# LED_SEQUENCER.net
KiCad netlist of a schematic drawn in Altium Designer
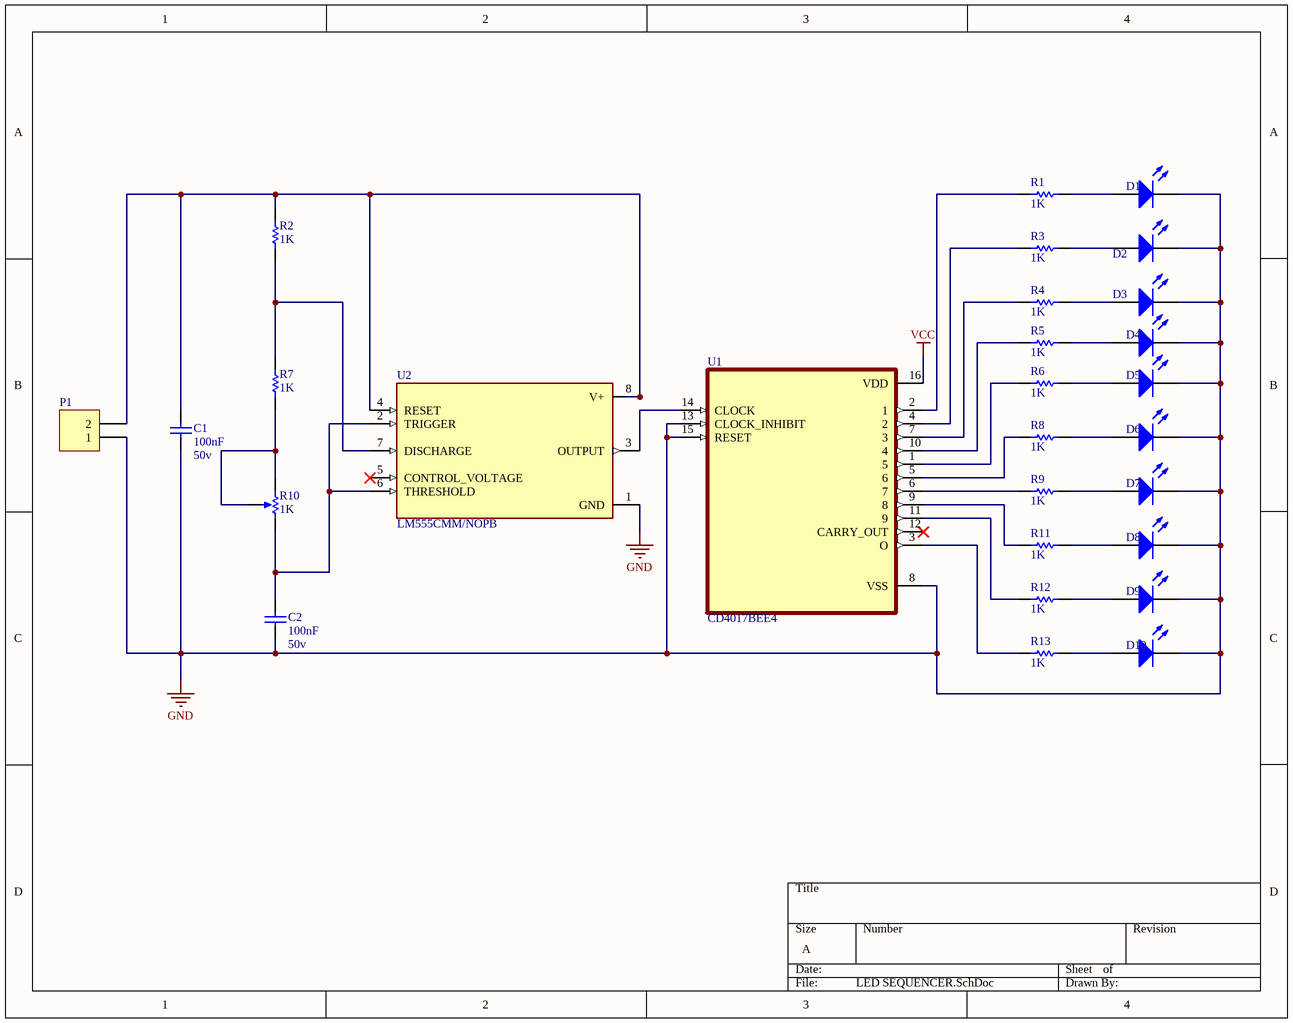
[diagram p0: LED SEQUENCER.SchDoc]

(export (version "E")
  (design (tool "Eeschema 10.0.6"))
  (components
    (comp (ref "C1")
      (value "100nF")
      (footprint "MY_0603")
      (description "None polar capacitor")
      (fields (field (name "ASID PART NUMBER") "C-AS") (field (name "VOLTE") "50v"))
      (libsource (lib "3. Mylib with 3d body") (part "Cap ceramic"))
    )
    (comp (ref "C2")
      (value "100nF")
      (footprint "MY_0603")
      (description "None polar capacitor")
      (fields (field (name "ASID PART NUMBER") "C-AS") (field (name "VOLTE") "50v"))
      (libsource (lib "3. Mylib with 3d body") (part "Cap ceramic"))
    )
    (comp (ref "D1")
      (value "~")
      (footprint "MY_LED_0805")
      (description "Typical INFRARED GaAs LED")
      (fields (field (name "ASID PART NUMBER") "LED-AS"))
      (libsource (lib "3. Mylib with 3d body") (part "LED"))
    )
    (comp (ref "D2")
      (value "~")
      (footprint "MY_LED_0805")
      (description "Typical INFRARED GaAs LED")
      (fields (field (name "ASID PART NUMBER") "LED-AS"))
      (libsource (lib "3. Mylib with 3d body") (part "LED"))
    )
    (comp (ref "D3")
      (value "~")
      (footprint "MY_LED_0805")
      (description "Typical INFRARED GaAs LED")
      (fields (field (name "ASID PART NUMBER") "LED-AS"))
      (libsource (lib "3. Mylib with 3d body") (part "LED"))
    )
    (comp (ref "D4")
      (value "~")
      (footprint "MY_LED_0805")
      (description "Typical INFRARED GaAs LED")
      (fields (field (name "ASID PART NUMBER") "LED-AS"))
      (libsource (lib "3. Mylib with 3d body") (part "LED"))
    )
    (comp (ref "D5")
      (value "~")
      (footprint "MY_LED_0805")
      (description "Typical INFRARED GaAs LED")
      (fields (field (name "ASID PART NUMBER") "LED-AS"))
      (libsource (lib "3. Mylib with 3d body") (part "LED"))
    )
    (comp (ref "D6")
      (value "~")
      (footprint "MY_LED_0805")
      (description "Typical INFRARED GaAs LED")
      (fields (field (name "ASID PART NUMBER") "LED-AS"))
      (libsource (lib "3. Mylib with 3d body") (part "LED"))
    )
    (comp (ref "D7")
      (value "~")
      (footprint "MY_LED_0805")
      (description "Typical INFRARED GaAs LED")
      (fields (field (name "ASID PART NUMBER") "LED-AS"))
      (libsource (lib "3. Mylib with 3d body") (part "LED"))
    )
    (comp (ref "D8")
      (value "~")
      (footprint "MY_LED_0805")
      (description "Typical INFRARED GaAs LED")
      (fields (field (name "ASID PART NUMBER") "LED-AS"))
      (libsource (lib "3. Mylib with 3d body") (part "LED"))
    )
    (comp (ref "D9")
      (value "~")
      (footprint "MY_LED_0805")
      (description "Typical INFRARED GaAs LED")
      (fields (field (name "ASID PART NUMBER") "LED-AS"))
      (libsource (lib "3. Mylib with 3d body") (part "LED"))
    )
    (comp (ref "D10")
      (value "~")
      (footprint "MY_LED_0805")
      (description "Typical INFRARED GaAs LED")
      (fields (field (name "ASID PART NUMBER") "LED-AS"))
      (libsource (lib "3. Mylib with 3d body") (part "LED"))
    )
    (comp (ref "P1")
      (value "Header 2")
      (footprint "MY_FE02")
      (description "Header, 2-Pin")
      (fields (field (name "ASID PART NUMBER") "Header 2-AS"))
      (libsource (lib "3. Mylib with 3d body") (part "Header 2"))
    )
    (comp (ref "R1")
      (value "1K")
      (footprint "MY_0603")
      (description "Standard resistor")
      (fields (field (name "ASID PART NUMBER") "Res-AS"))
      (libsource (lib "3. Mylib with 3d body") (part "Res"))
    )
    (comp (ref "R2")
      (value "1K")
      (footprint "MY_0603")
      (description "Standard resistor")
      (fields (field (name "ASID PART NUMBER") "Res-AS"))
      (libsource (lib "3. Mylib with 3d body") (part "Res"))
    )
    (comp (ref "R3")
      (value "1K")
      (footprint "MY_0603")
      (description "Standard resistor")
      (fields (field (name "ASID PART NUMBER") "Res-AS"))
      (libsource (lib "3. Mylib with 3d body") (part "Res"))
    )
    (comp (ref "R4")
      (value "1K")
      (footprint "MY_0603")
      (description "Standard resistor")
      (fields (field (name "ASID PART NUMBER") "Res-AS"))
      (libsource (lib "3. Mylib with 3d body") (part "Res"))
    )
    (comp (ref "R5")
      (value "1K")
      (footprint "MY_0603")
      (description "Standard resistor")
      (fields (field (name "ASID PART NUMBER") "Res-AS"))
      (libsource (lib "3. Mylib with 3d body") (part "Res"))
    )
    (comp (ref "R6")
      (value "1K")
      (footprint "MY_0603")
      (description "Standard resistor")
      (fields (field (name "ASID PART NUMBER") "Res-AS"))
      (libsource (lib "3. Mylib with 3d body") (part "Res"))
    )
    (comp (ref "R7")
      (value "1K")
      (footprint "MY_0603")
      (description "Standard resistor")
      (fields (field (name "ASID PART NUMBER") "Res-AS"))
      (libsource (lib "3. Mylib with 3d body") (part "Res"))
    )
    (comp (ref "R8")
      (value "1K")
      (footprint "MY_0603")
      (description "Standard resistor")
      (fields (field (name "ASID PART NUMBER") "Res-AS"))
      (libsource (lib "3. Mylib with 3d body") (part "Res"))
    )
    (comp (ref "R9")
      (value "1K")
      (footprint "MY_0603")
      (description "Standard resistor")
      (fields (field (name "ASID PART NUMBER") "Res-AS"))
      (libsource (lib "3. Mylib with 3d body") (part "Res"))
    )
    (comp (ref "R10")
      (value "1K")
      (footprint "My_Pot")
      (description "Potentiometer")
      (fields (field (name "ASID PART NUMBER") "Variable Resistor-AS"))
      (libsource (lib "3. Mylib with 3d body") (part "Variable Resistor"))
    )
    (comp (ref "R11")
      (value "1K")
      (footprint "MY_0603")
      (description "Standard resistor")
      (fields (field (name "ASID PART NUMBER") "Res-AS"))
      (libsource (lib "3. Mylib with 3d body") (part "Res"))
    )
    (comp (ref "R12")
      (value "1K")
      (footprint "MY_0603")
      (description "Standard resistor")
      (fields (field (name "ASID PART NUMBER") "Res-AS"))
      (libsource (lib "3. Mylib with 3d body") (part "Res"))
    )
    (comp (ref "R13")
      (value "1K")
      (footprint "MY_0603")
      (description "Standard resistor")
      (fields (field (name "ASID PART NUMBER") "Res-AS"))
      (libsource (lib "3. Mylib with 3d body") (part "Res"))
    )
    (comp (ref "U1")
      (value "CD4017BEE4")
      (footprint "DIP794W45P254L1969H508Q16")
      (description "CMOS Decade Counter with 10 Decoded Outputs 16-PDIP -55 to 125")
      (fields (field (name "MF") "Texas Instruments"))
      (libsource (lib "CD4017BEE4") (part "CD4017BEE4"))
    )
    (comp (ref "U2")
      (value "LM555CMM/NOPB")
      (footprint "SOP65P490X110-8N")
      (description "Highly Stable 555 Timer")
      (fields (field (name "MF") "Texas Instruments"))
      (libsource (lib "LM555CMM_NOPB") (part "LM555CMM/NOPB"))
    )
  )
  (nets
    (net (code "1") (name "GND") (class "Default")
      (node (ref "C1") (pin "1") (pinfunction "1_1") (pintype "passive"))
      (node (ref "C2") (pin "1") (pinfunction "1_1") (pintype "passive"))
      (node (ref "D1") (pin "K") (pinfunction "K_K") (pintype "passive"))
      (node (ref "D10") (pin "K") (pinfunction "K_K") (pintype "passive"))
      (node (ref "D2") (pin "K") (pinfunction "K_K") (pintype "passive"))
      (node (ref "D3") (pin "K") (pinfunction "K_K") (pintype "passive"))
      (node (ref "D4") (pin "K") (pinfunction "K_K") (pintype "passive"))
      (node (ref "D5") (pin "K") (pinfunction "K_K") (pintype "passive"))
      (node (ref "D6") (pin "K") (pinfunction "K_K") (pintype "passive"))
      (node (ref "D7") (pin "K") (pinfunction "K_K") (pintype "passive"))
      (node (ref "D8") (pin "K") (pinfunction "K_K") (pintype "passive"))
      (node (ref "D9") (pin "K") (pinfunction "K_K") (pintype "passive"))
      (node (ref "P1") (pin "1") (pinfunction "1_1") (pintype "passive"))
      (node (ref "U1") (pin "13") (pinfunction "CLOCK_INHIBIT_13") (pintype "input"))
      (node (ref "U1") (pin "15") (pinfunction "RESET_15") (pintype "input"))
      (node (ref "U1") (pin "8") (pinfunction "VSS_8") (pintype "power_in"))
      (node (ref "U2") (pin "1") (pinfunction "GND_1") (pintype "power_in"))
    )
    (net (code "2") (name "Net-(D1-PadA)") (class "Default")
      (node (ref "D1") (pin "A") (pinfunction "A_A") (pintype "passive"))
      (node (ref "R1") (pin "2") (pinfunction "2_2") (pintype "passive"))
    )
    (net (code "3") (name "Net-(D2-PadA)") (class "Default")
      (node (ref "D2") (pin "A") (pinfunction "A_A") (pintype "passive"))
      (node (ref "R3") (pin "2") (pinfunction "2_2") (pintype "passive"))
    )
    (net (code "4") (name "Net-(D3-PadA)") (class "Default")
      (node (ref "D3") (pin "A") (pinfunction "A_A") (pintype "passive"))
      (node (ref "R4") (pin "2") (pinfunction "2_2") (pintype "passive"))
    )
    (net (code "5") (name "Net-(D4-PadA)") (class "Default")
      (node (ref "D4") (pin "A") (pinfunction "A_A") (pintype "passive"))
      (node (ref "R5") (pin "2") (pinfunction "2_2") (pintype "passive"))
    )
    (net (code "6") (name "Net-(D5-PadA)") (class "Default")
      (node (ref "D5") (pin "A") (pinfunction "A_A") (pintype "passive"))
      (node (ref "R6") (pin "2") (pinfunction "2_2") (pintype "passive"))
    )
    (net (code "7") (name "Net-(D6-PadA)") (class "Default")
      (node (ref "D6") (pin "A") (pinfunction "A_A") (pintype "passive"))
      (node (ref "R8") (pin "2") (pinfunction "2_2") (pintype "passive"))
    )
    (net (code "8") (name "Net-(D7-PadA)") (class "Default")
      (node (ref "D7") (pin "A") (pinfunction "A_A") (pintype "passive"))
      (node (ref "R9") (pin "2") (pinfunction "2_2") (pintype "passive"))
    )
    (net (code "9") (name "Net-(D8-PadA)") (class "Default")
      (node (ref "D8") (pin "A") (pinfunction "A_A") (pintype "passive"))
      (node (ref "R11") (pin "2") (pinfunction "2_2") (pintype "passive"))
    )
    (net (code "10") (name "Net-(D9-PadA)") (class "Default")
      (node (ref "D9") (pin "A") (pinfunction "A_A") (pintype "passive"))
      (node (ref "R12") (pin "2") (pinfunction "2_2") (pintype "passive"))
    )
    (net (code "11") (name "Net-(D10-PadA)") (class "Default")
      (node (ref "D10") (pin "A") (pinfunction "A_A") (pintype "passive"))
      (node (ref "R13") (pin "2") (pinfunction "2_2") (pintype "passive"))
    )
    (net (code "12") (name "Net-(R10-BOT)") (class "Default")
      (node (ref "C2") (pin "2") (pinfunction "2_2") (pintype "passive"))
      (node (ref "R10") (pin "2") (pinfunction "BOT_2") (pintype "passive"))
      (node (ref "U2") (pin "2") (pinfunction "TRIGGER_2") (pintype "input"))
      (node (ref "U2") (pin "6") (pinfunction "THRESHOLD_6") (pintype "input"))
    )
    (net (code "13") (name "Net-(R10-TAP)") (class "Default")
      (node (ref "R10") (pin "1") (pinfunction "TOP_1") (pintype "passive"))
      (node (ref "R10") (pin "3") (pinfunction "TAP_3") (pintype "passive"))
      (node (ref "R7") (pin "2") (pinfunction "2_2") (pintype "passive"))
    )
    (net (code "14") (name "Net-(U1-1)") (class "Default")
      (node (ref "R1") (pin "1") (pinfunction "1_1") (pintype "passive"))
      (node (ref "U1") (pin "2") (pinfunction "1_2") (pintype "output"))
    )
    (net (code "15") (name "Net-(U1-2)") (class "Default")
      (node (ref "R3") (pin "1") (pinfunction "1_1") (pintype "passive"))
      (node (ref "U1") (pin "4") (pinfunction "2_4") (pintype "output"))
    )
    (net (code "16") (name "Net-(U1-3)") (class "Default")
      (node (ref "R4") (pin "1") (pinfunction "1_1") (pintype "passive"))
      (node (ref "U1") (pin "7") (pinfunction "3_7") (pintype "output"))
    )
    (net (code "17") (name "Net-(U1-4)") (class "Default")
      (node (ref "R5") (pin "1") (pinfunction "1_1") (pintype "passive"))
      (node (ref "U1") (pin "10") (pinfunction "4_10") (pintype "output"))
    )
    (net (code "18") (name "Net-(U1-5)") (class "Default")
      (node (ref "R6") (pin "1") (pinfunction "1_1") (pintype "passive"))
      (node (ref "U1") (pin "1") (pinfunction "5_1") (pintype "output"))
    )
    (net (code "19") (name "Net-(U1-6)") (class "Default")
      (node (ref "R8") (pin "1") (pinfunction "1_1") (pintype "passive"))
      (node (ref "U1") (pin "5") (pinfunction "6_5") (pintype "output"))
    )
    (net (code "20") (name "Net-(U1-7)") (class "Default")
      (node (ref "R9") (pin "1") (pinfunction "1_1") (pintype "passive"))
      (node (ref "U1") (pin "6") (pinfunction "7_6") (pintype "output"))
    )
    (net (code "21") (name "Net-(U1-8)") (class "Default")
      (node (ref "R11") (pin "1") (pinfunction "1_1") (pintype "passive"))
      (node (ref "U1") (pin "9") (pinfunction "8_9") (pintype "output"))
    )
    (net (code "22") (name "Net-(U1-9)") (class "Default")
      (node (ref "R12") (pin "1") (pinfunction "1_1") (pintype "passive"))
      (node (ref "U1") (pin "11") (pinfunction "9_11") (pintype "output"))
    )
    (net (code "23") (name "Net-(U1-CLOCK)") (class "Default")
      (node (ref "U1") (pin "14") (pinfunction "CLOCK_14") (pintype "input"))
      (node (ref "U2") (pin "3") (pinfunction "OUTPUT_3") (pintype "output"))
    )
    (net (code "24") (name "Net-(U1-O)") (class "Default")
      (node (ref "R13") (pin "1") (pinfunction "1_1") (pintype "passive"))
      (node (ref "U1") (pin "3") (pinfunction "O_3") (pintype "output"))
    )
    (net (code "25") (name "Net-(U2-DISCHARGE)") (class "Default")
      (node (ref "R2") (pin "2") (pinfunction "2_2") (pintype "passive"))
      (node (ref "R7") (pin "1") (pinfunction "1_1") (pintype "passive"))
      (node (ref "U2") (pin "7") (pinfunction "DISCHARGE_7") (pintype "input"))
    )
    (net (code "26") (name "Net-(U2-RESET)") (class "Default")
      (node (ref "C1") (pin "2") (pinfunction "2_2") (pintype "passive"))
      (node (ref "P1") (pin "2") (pinfunction "2_2") (pintype "passive"))
      (node (ref "R2") (pin "1") (pinfunction "1_1") (pintype "passive"))
      (node (ref "U2") (pin "4") (pinfunction "RESET_4") (pintype "input"))
      (node (ref "U2") (pin "8") (pinfunction "V+_8") (pintype "power_in"))
    )
    (net (code "27") (name "VCC") (class "Default")
      (node (ref "U1") (pin "16") (pinfunction "VDD_16") (pintype "power_in"))
    )
    (net (code "28") (name "unconnected-(U1-CARRY_OUT-Pad12)") (class "Default")
      (node (ref "U1") (pin "12") (pinfunction "CARRY_OUT_12") (pintype "output+no_connect"))
    )
    (net (code "29") (name "unconnected-(U2-CONTROL_VOLTAGE-Pad5)") (class "Default")
      (node (ref "U2") (pin "5") (pinfunction "CONTROL_VOLTAGE_5") (pintype "input+no_connect"))
    )
  )
)
